# MSP432P401R.net
KiCad netlist of a schematic drawn in Altium Designer
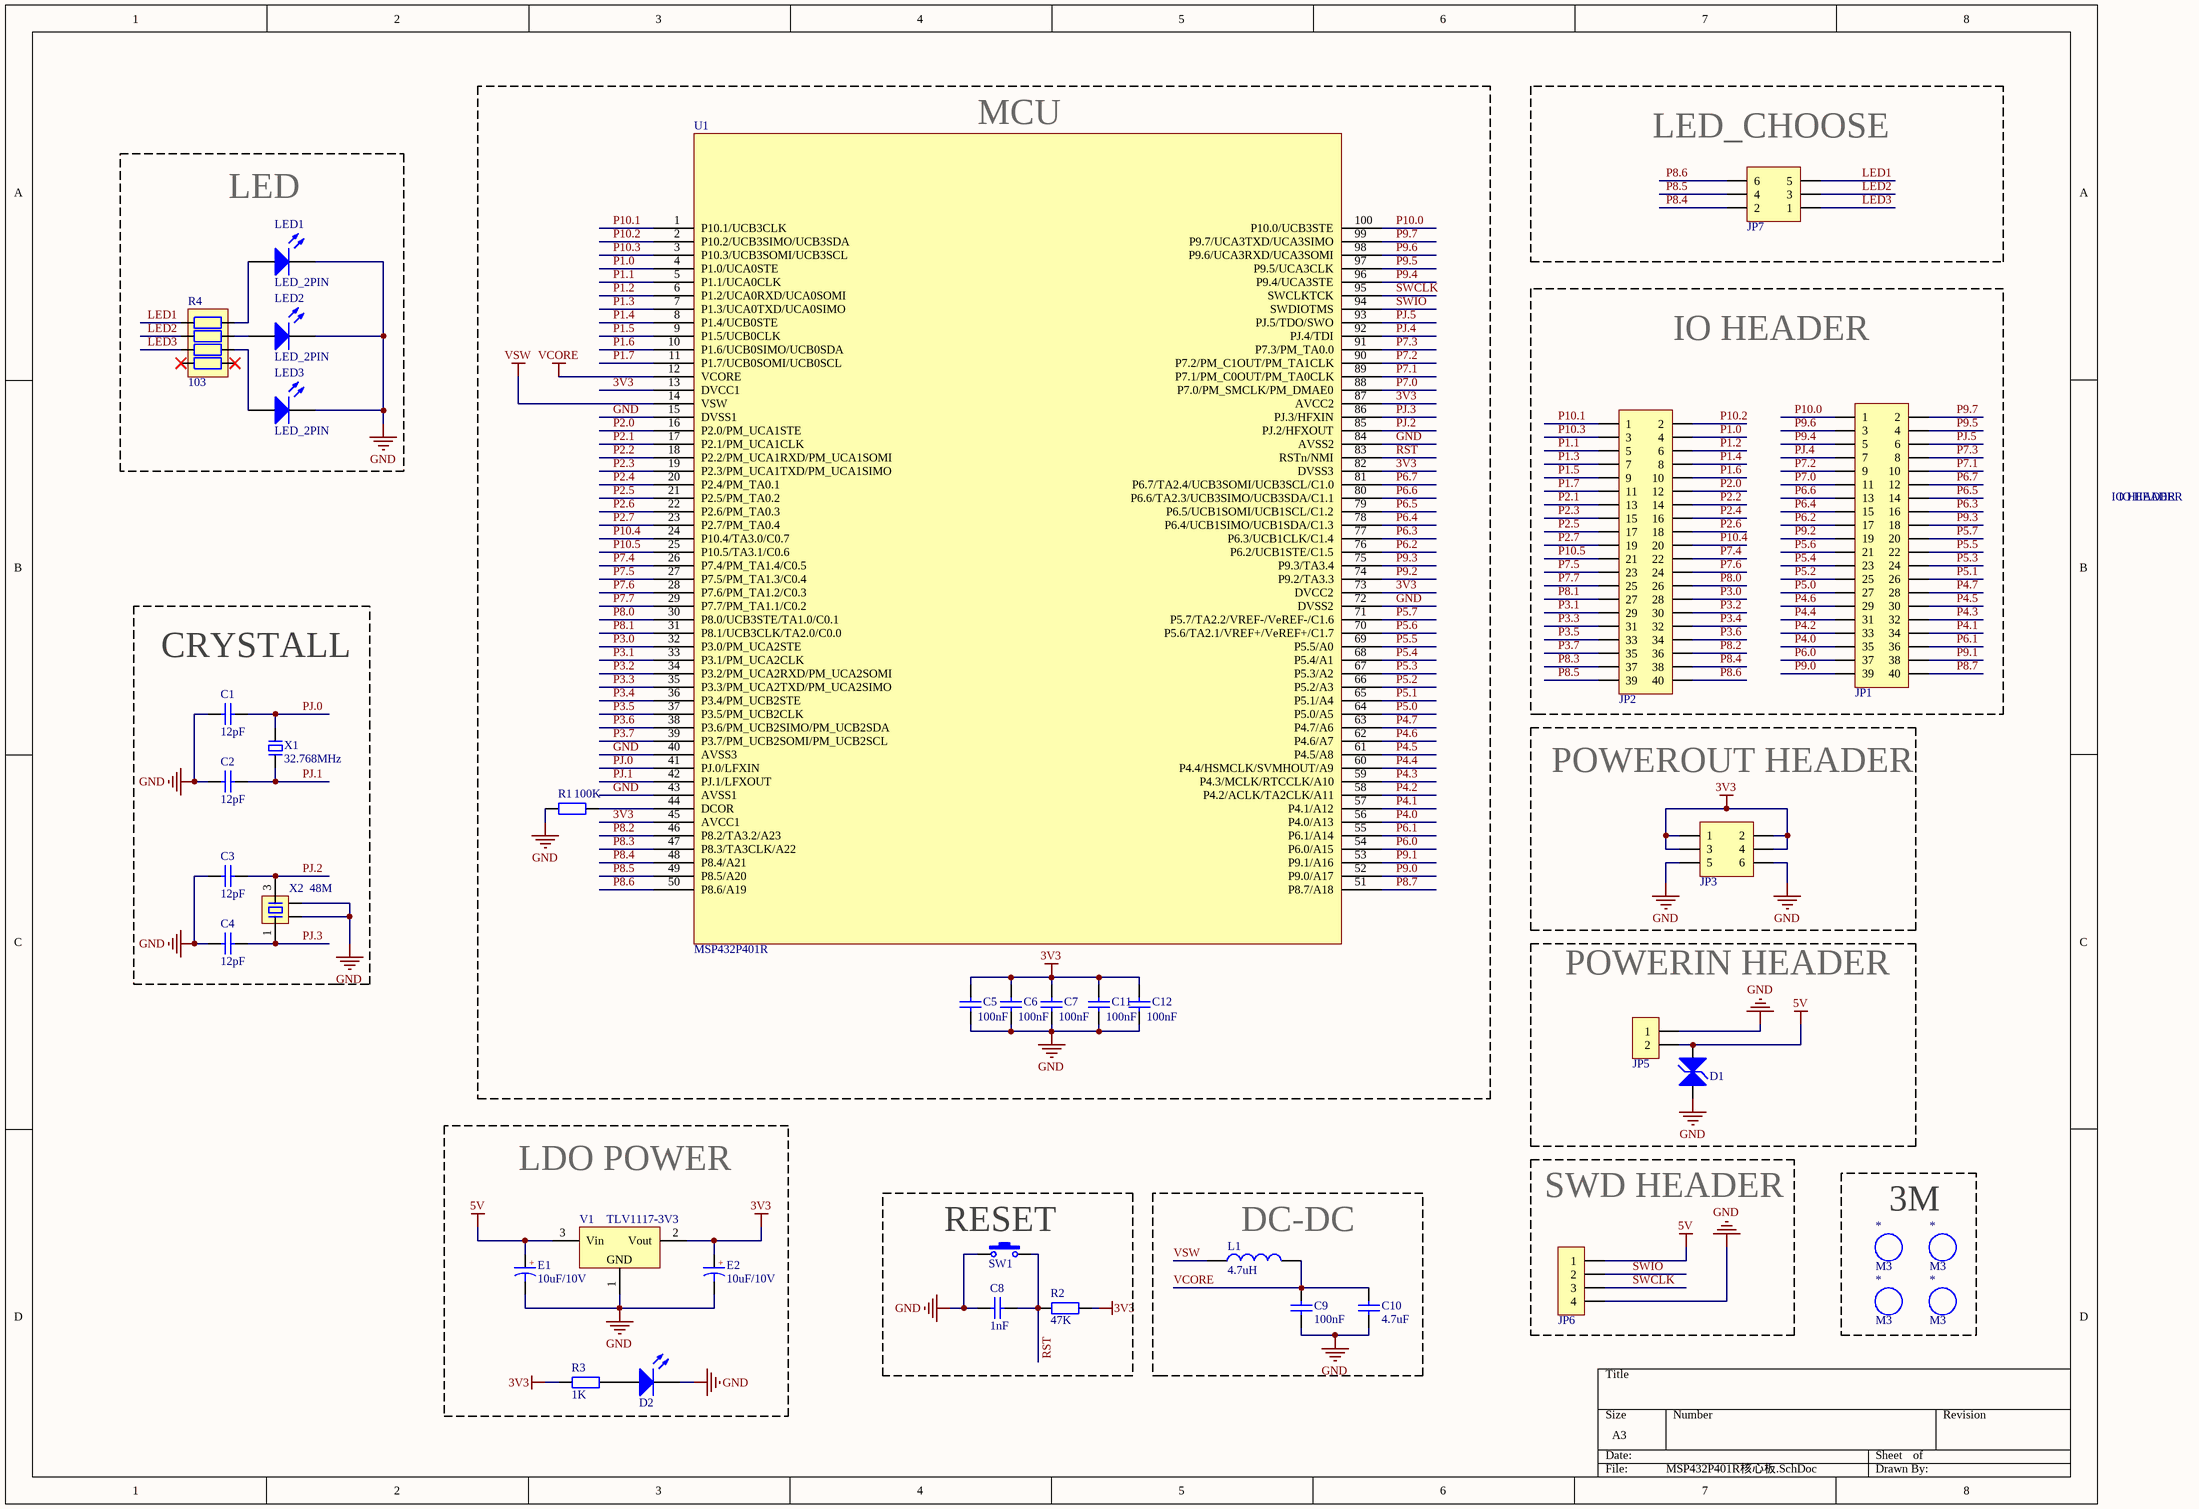
[diagram p0: MSP432P401R核心板.SchDoc]

(export (version "E")
  (design (tool "Eeschema 10.0.6"))
  (components
    (comp (ref "C1")
      (value "12pF")
      (footprint "C0603_L")
      (description "贴片电容")
      (libsource (lib "0.1 - 电阻-电容-电感") (part "C"))
    )
    (comp (ref "C2")
      (value "12pF")
      (footprint "C0603_L")
      (description "贴片电容")
      (libsource (lib "0.1 - 电阻-电容-电感") (part "C"))
    )
    (comp (ref "C3")
      (value "12pF")
      (footprint "C0603_L")
      (description "贴片电容")
      (libsource (lib "0.1 - 电阻-电容-电感") (part "C"))
    )
    (comp (ref "C4")
      (value "12pF")
      (footprint "C0603_L")
      (description "贴片电容")
      (libsource (lib "0.1 - 电阻-电容-电感") (part "C"))
    )
    (comp (ref "C5")
      (value "100nF")
      (footprint "C0603_L")
      (description "贴片电容")
      (libsource (lib "0.1 - 电阻-电容-电感") (part "C"))
    )
    (comp (ref "C6")
      (value "100nF")
      (footprint "C0603_L")
      (description "贴片电容")
      (libsource (lib "0.1 - 电阻-电容-电感") (part "C"))
    )
    (comp (ref "C7")
      (value "100nF")
      (footprint "C0603_L")
      (description "贴片电容")
      (libsource (lib "0.1 - 电阻-电容-电感") (part "C"))
    )
    (comp (ref "C8")
      (value "1nF")
      (footprint "C0603_L")
      (description "贴片电容")
      (libsource (lib "0.1 - 电阻-电容-电感") (part "C"))
    )
    (comp (ref "C9")
      (value "100nF")
      (footprint "C0603_L")
      (description "贴片电容")
      (libsource (lib "0.1 - 电阻-电容-电感") (part "C"))
    )
    (comp (ref "C10")
      (value "4.7uF")
      (footprint "C0603_L")
      (description "贴片电容")
      (libsource (lib "0.1 - 电阻-电容-电感") (part "C"))
    )
    (comp (ref "C11")
      (value "100nF")
      (footprint "C0603_L")
      (description "贴片电容")
      (libsource (lib "0.1 - 电阻-电容-电感") (part "C"))
    )
    (comp (ref "C12")
      (value "100nF")
      (footprint "C0603_L")
      (description "贴片电容")
      (libsource (lib "0.1 - 电阻-电容-电感") (part "C"))
    )
    (comp (ref "D1")
      (value "TVS")
      (footprint "SMA")
      (description "TVS保护")
      (libsource (lib "0.2 - 二极管-整流桥") (part "TVS"))
    )
    (comp (ref "D2")
      (value "LED")
      (footprint "LED0603_B")
      (description "发光二极管")
      (libsource (lib "0.3 - LED发光二极管") (part "LED"))
    )
    (comp (ref "E1")
      (value "10uF/10V")
      (footprint "CS 6*6 - B")
      (description "贴片固态电容")
      (libsource (lib "0.1 - 电阻-电容-电感") (part "CS_SMD"))
    )
    (comp (ref "E2")
      (value "10uF/10V")
      (footprint "CS 6*6 - B")
      (description "贴片固态电容")
      (libsource (lib "0.1 - 电阻-电容-电感") (part "CS_SMD"))
    )
    (comp (ref "JP1")
      (value "Header 2X11")
      (footprint "HDR2.54-LI-2x20P")
      (description "20*2P接插件")
      (libsource (lib "5.4 - 接插件-脚距2.54 (100mil) ") (part "Header 20X2"))
    )
    (comp (ref "JP2")
      (value "Header 2X11")
      (footprint "HDR2.54-LI-2x20P")
      (description "20*2P接插件")
      (libsource (lib "5.4 - 接插件-脚距2.54 (100mil) ") (part "Header 20X2"))
    )
    (comp (ref "JP3")
      (value "Header3X2")
      (footprint "HDR2.54-LI-2x3P")
      (description "3*2P接插件")
      (libsource (lib "") (part "Header 3X2_1"))
    )
    (comp (ref "JP5")
      (value "HDR-1X2")
      (footprint "PH2.0-WS-2P")
      (description "2P接插件")
      (libsource (lib "5.3 - 接插件-脚距2.0") (part "Header 2"))
    )
    (comp (ref "JP6")
      (value "HDR-1X4")
      (footprint "PH2.0-WS-4P")
      (description "4P接插件")
      (libsource (lib "5.3 - 接插件-脚距2.0") (part "Header 4"))
    )
    (comp (ref "JP7")
      (value "Header3X2")
      (footprint "HDR2.54-LI-2x3P")
      (description "3*2P接插件")
      (libsource (lib "5.4 - 接插件-脚距2.54 (100mil) ") (part "Header 3X2"))
    )
    (comp (ref "L1")
      (value "4.7uH")
      (footprint "L0603")
      (description "贴片小功率电感")
      (libsource (lib "0.1 - 电阻-电容-电感") (part "L"))
    )
    (comp (ref "LED1")
      (value "LED_2PIN")
      (footprint "LED0603_B")
      (description "2脚LED")
      (libsource (lib "0.3 - LED发光二极管") (part "LED_2PIN"))
    )
    (comp (ref "LED2")
      (value "LED_2PIN")
      (footprint "LED0603_G")
      (description "2脚LED")
      (libsource (lib "0.3 - LED发光二极管") (part "LED_2PIN"))
    )
    (comp (ref "LED3")
      (value "LED_2PIN")
      (footprint "LED0603_Y")
      (description "2脚LED")
      (libsource (lib "0.3 - LED发光二极管") (part "LED_2PIN"))
    )
    (comp (ref "R1")
      (value "100K")
      (footprint "R0603_L")
      (description "贴片电阻")
      (libsource (lib "0.1 - 电阻-电容-电感") (part "R"))
    )
    (comp (ref "R2")
      (value "47K")
      (footprint "R0603_L")
      (description "贴片电阻")
      (libsource (lib "0.1 - 电阻-电容-电感") (part "R"))
    )
    (comp (ref "R3")
      (value "1K")
      (footprint "R0603_L")
      (description "贴片电阻")
      (libsource (lib "0.1 - 电阻-电容-电感") (part "R"))
    )
    (comp (ref "R4")
      (value "103")
      (footprint "RCA-8P4R-0603")
      (description "贴片排阻")
      (libsource (lib "0.1 - 电阻-电容-电感") (part "R-8P4R"))
    )
    (comp (ref "SW1")
      (value "3x6x5")
      (footprint "SW SMD-3*6*2.5")
      (description "3x6轻触开关")
      (libsource (lib "0.7 - 常用按键-开关-蜂鸣器-电池") (part "TSW_2PIN"))
    )
    (comp (ref "U1")
      (value "MSP432P401R")
      (footprint "QFP100")
      (libsource (lib "3.7 - MSP430系列单片机") (part "MSP432P401R"))
    )
    (comp (ref "V1")
      (value "TLV1117-3V3")
      (footprint "SOT223_L")
      (description "三端稳压芯片")
      (libsource (lib "1.1 - 电源类芯片") (part "AMS1117"))
    )
    (comp (ref "X1")
      (value "32.768MHz")
      (footprint "OSC 3215-2P")
      (description "2脚无源脚晶振")
      (libsource (lib "0.5 - 保险丝-晶振-光耦") (part "XTAL-2P"))
    )
    (comp (ref "X2")
      (value "48M")
      (footprint "OSC 3225-4P")
      (description "4脚晶振")
      (libsource (lib "0.5 - 保险丝-晶振-光耦") (part "XTAL-4P"))
    )
  )
  (nets
    (net (code "1") (name "/LED1") (class "Default")
      (node (ref "JP7") (pin "5") (pinfunction "5_5") (pintype "passive"))
      (node (ref "R4") (pin "1") (pinfunction "1_1") (pintype "passive"))
    )
    (net (code "2") (name "/LED2") (class "Default")
      (node (ref "JP7") (pin "3") (pinfunction "3_3") (pintype "passive"))
      (node (ref "R4") (pin "2") (pinfunction "2_2") (pintype "passive"))
    )
    (net (code "3") (name "/LED3") (class "Default")
      (node (ref "JP7") (pin "1") (pinfunction "1_1") (pintype "passive"))
      (node (ref "R4") (pin "3") (pinfunction "3_3") (pintype "passive"))
    )
    (net (code "4") (name "/P1.0") (class "Default")
      (node (ref "JP2") (pin "4") (pinfunction "4_4") (pintype "passive"))
      (node (ref "U1") (pin "4") (pinfunction "P1.0/UCA0STE_4") (pintype "passive"))
    )
    (net (code "5") (name "/P1.1") (class "Default")
      (node (ref "JP2") (pin "5") (pinfunction "5_5") (pintype "passive"))
      (node (ref "U1") (pin "5") (pinfunction "P1.1/UCA0CLK_5") (pintype "passive"))
    )
    (net (code "6") (name "/P1.2") (class "Default")
      (node (ref "JP2") (pin "6") (pinfunction "6_6") (pintype "passive"))
      (node (ref "U1") (pin "6") (pinfunction "P1.2/UCA0RXD/UCA0SOMI_6") (pintype "passive"))
    )
    (net (code "7") (name "/P1.3") (class "Default")
      (node (ref "JP2") (pin "7") (pinfunction "7_7") (pintype "passive"))
      (node (ref "U1") (pin "7") (pinfunction "P1.3/UCA0TXD/UCA0SIMO_7") (pintype "passive"))
    )
    (net (code "8") (name "/P1.4") (class "Default")
      (node (ref "JP2") (pin "8") (pinfunction "8_8") (pintype "passive"))
      (node (ref "U1") (pin "8") (pinfunction "P1.4/UCB0STE_8") (pintype "passive"))
    )
    (net (code "9") (name "/P1.5") (class "Default")
      (node (ref "JP2") (pin "9") (pinfunction "9_9") (pintype "passive"))
      (node (ref "U1") (pin "9") (pinfunction "P1.5/UCB0CLK_9") (pintype "passive"))
    )
    (net (code "10") (name "/P1.6") (class "Default")
      (node (ref "JP2") (pin "10") (pinfunction "10_10") (pintype "passive"))
      (node (ref "U1") (pin "10") (pinfunction "P1.6/UCB0SIMO/UCB0SDA_10") (pintype "passive"))
    )
    (net (code "11") (name "/P1.7") (class "Default")
      (node (ref "JP2") (pin "11") (pinfunction "11_11") (pintype "passive"))
      (node (ref "U1") (pin "11") (pinfunction "P1.7/UCB0SOMI/UCB0SCL_11") (pintype "passive"))
    )
    (net (code "12") (name "/P2.0") (class "Default")
      (node (ref "JP2") (pin "12") (pinfunction "12_12") (pintype "passive"))
      (node (ref "U1") (pin "16") (pinfunction "P2.0/PM_UCA1STE_16") (pintype "passive"))
    )
    (net (code "13") (name "/P2.1") (class "Default")
      (node (ref "JP2") (pin "13") (pinfunction "13_13") (pintype "passive"))
      (node (ref "U1") (pin "17") (pinfunction "P2.1/PM_UCA1CLK_17") (pintype "passive"))
    )
    (net (code "14") (name "/P2.2") (class "Default")
      (node (ref "JP2") (pin "14") (pinfunction "14_14") (pintype "passive"))
      (node (ref "U1") (pin "18") (pinfunction "P2.2/PM_UCA1RXD/PM_UCA1SOMI_18") (pintype "passive"))
    )
    (net (code "15") (name "/P2.3") (class "Default")
      (node (ref "JP2") (pin "15") (pinfunction "15_15") (pintype "passive"))
      (node (ref "U1") (pin "19") (pinfunction "P2.3/PM_UCA1TXD/PM_UCA1SIMO_19") (pintype "passive"))
    )
    (net (code "16") (name "/P2.4") (class "Default")
      (node (ref "JP2") (pin "16") (pinfunction "16_16") (pintype "passive"))
      (node (ref "U1") (pin "20") (pinfunction "P2.4/PM_TA0.1_20") (pintype "passive"))
    )
    (net (code "17") (name "/P2.5") (class "Default")
      (node (ref "JP2") (pin "17") (pinfunction "17_17") (pintype "passive"))
      (node (ref "U1") (pin "21") (pinfunction "P2.5/PM_TA0.2_21") (pintype "passive"))
    )
    (net (code "18") (name "/P2.6") (class "Default")
      (node (ref "JP2") (pin "18") (pinfunction "18_18") (pintype "passive"))
      (node (ref "U1") (pin "22") (pinfunction "P2.6/PM_TA0.3_22") (pintype "passive"))
    )
    (net (code "19") (name "/P2.7") (class "Default")
      (node (ref "JP2") (pin "19") (pinfunction "19_19") (pintype "passive"))
      (node (ref "U1") (pin "23") (pinfunction "P2.7/PM_TA0.4_23") (pintype "passive"))
    )
    (net (code "20") (name "/P3.0") (class "Default")
      (node (ref "JP2") (pin "28") (pinfunction "28_28") (pintype "passive"))
      (node (ref "U1") (pin "32") (pinfunction "P3.0/PM_UCA2STE_32") (pintype "passive"))
    )
    (net (code "21") (name "/P3.1") (class "Default")
      (node (ref "JP2") (pin "29") (pinfunction "29_29") (pintype "passive"))
      (node (ref "U1") (pin "33") (pinfunction "P3.1/PM_UCA2CLK_33") (pintype "passive"))
    )
    (net (code "22") (name "/P3.2") (class "Default")
      (node (ref "JP2") (pin "30") (pinfunction "30_30") (pintype "passive"))
      (node (ref "U1") (pin "34") (pinfunction "P3.2/PM_UCA2RXD/PM_UCA2SOMI_34") (pintype "passive"))
    )
    (net (code "23") (name "/P3.3") (class "Default")
      (node (ref "JP2") (pin "31") (pinfunction "31_31") (pintype "passive"))
      (node (ref "U1") (pin "35") (pinfunction "P3.3/PM_UCA2TXD/PM_UCA2SIMO_35") (pintype "passive"))
    )
    (net (code "24") (name "/P3.4") (class "Default")
      (node (ref "JP2") (pin "32") (pinfunction "32_32") (pintype "passive"))
      (node (ref "U1") (pin "36") (pinfunction "P3.4/PM_UCB2STE_36") (pintype "passive"))
    )
    (net (code "25") (name "/P3.5") (class "Default")
      (node (ref "JP2") (pin "33") (pinfunction "33_33") (pintype "passive"))
      (node (ref "U1") (pin "37") (pinfunction "P3.5/PM_UCB2CLK_37") (pintype "passive"))
    )
    (net (code "26") (name "/P3.6") (class "Default")
      (node (ref "JP2") (pin "34") (pinfunction "34_34") (pintype "passive"))
      (node (ref "U1") (pin "38") (pinfunction "P3.6/PM_UCB2SIMO/PM_UCB2SDA_38") (pintype "passive"))
    )
    (net (code "27") (name "/P3.7") (class "Default")
      (node (ref "JP2") (pin "35") (pinfunction "35_35") (pintype "passive"))
      (node (ref "U1") (pin "39") (pinfunction "P3.7/PM_UCB2SOMI/PM_UCB2SCL_39") (pintype "passive"))
    )
    (net (code "28") (name "/P4.0") (class "Default")
      (node (ref "JP1") (pin "35") (pinfunction "35_35") (pintype "passive"))
      (node (ref "U1") (pin "56") (pinfunction "_P4.0/A13_56") (pintype "passive"))
    )
    (net (code "29") (name "/P4.1") (class "Default")
      (node (ref "JP1") (pin "34") (pinfunction "34_34") (pintype "passive"))
      (node (ref "U1") (pin "57") (pinfunction "P4.1/A12_57") (pintype "passive"))
    )
    (net (code "30") (name "/P4.2") (class "Default")
      (node (ref "JP1") (pin "33") (pinfunction "33_33") (pintype "passive"))
      (node (ref "U1") (pin "58") (pinfunction "_P4.2/ACLK/TA2CLK/A11_58") (pintype "passive"))
    )
    (net (code "31") (name "/P4.3") (class "Default")
      (node (ref "JP1") (pin "32") (pinfunction "32_32") (pintype "passive"))
      (node (ref "U1") (pin "59") (pinfunction "P4.3/MCLK/RTCCLK/A10_59") (pintype "passive"))
    )
    (net (code "32") (name "/P4.4") (class "Default")
      (node (ref "JP1") (pin "31") (pinfunction "31_31") (pintype "passive"))
      (node (ref "U1") (pin "60") (pinfunction "P4.4/HSMCLK/SVMHOUT/A9_60") (pintype "passive"))
    )
    (net (code "33") (name "/P4.5") (class "Default")
      (node (ref "JP1") (pin "30") (pinfunction "30_30") (pintype "passive"))
      (node (ref "U1") (pin "61") (pinfunction "P4.5/A8_61") (pintype "passive"))
    )
    (net (code "34") (name "/P4.6") (class "Default")
      (node (ref "JP1") (pin "29") (pinfunction "29_29") (pintype "passive"))
      (node (ref "U1") (pin "62") (pinfunction "P4.6/A7_62") (pintype "passive"))
    )
    (net (code "35") (name "/P4.7") (class "Default")
      (node (ref "JP1") (pin "28") (pinfunction "28_28") (pintype "passive"))
      (node (ref "U1") (pin "63") (pinfunction "P4.7/A6_63") (pintype "passive"))
    )
    (net (code "36") (name "/P5.0") (class "Default")
      (node (ref "JP1") (pin "27") (pinfunction "27_27") (pintype "passive"))
      (node (ref "U1") (pin "64") (pinfunction "P5.0/A5_64") (pintype "passive"))
    )
    (net (code "37") (name "/P5.1") (class "Default")
      (node (ref "JP1") (pin "26") (pinfunction "26_26") (pintype "passive"))
      (node (ref "U1") (pin "65") (pinfunction "P5.1/A4_65") (pintype "passive"))
    )
    (net (code "38") (name "/P5.2") (class "Default")
      (node (ref "JP1") (pin "25") (pinfunction "25_25") (pintype "passive"))
      (node (ref "U1") (pin "66") (pinfunction "P5.2/A3_66") (pintype "passive"))
    )
    (net (code "39") (name "/P5.3") (class "Default")
      (node (ref "JP1") (pin "24") (pinfunction "24_24") (pintype "passive"))
      (node (ref "U1") (pin "67") (pinfunction "P5.3/A2_67") (pintype "passive"))
    )
    (net (code "40") (name "/P5.4") (class "Default")
      (node (ref "JP1") (pin "23") (pinfunction "23_23") (pintype "passive"))
      (node (ref "U1") (pin "68") (pinfunction "P5.4/A1_68") (pintype "passive"))
    )
    (net (code "41") (name "/P5.5") (class "Default")
      (node (ref "JP1") (pin "22") (pinfunction "22_22") (pintype "passive"))
      (node (ref "U1") (pin "69") (pinfunction "P5.5/A0_69") (pintype "passive"))
    )
    (net (code "42") (name "/P5.6") (class "Default")
      (node (ref "JP1") (pin "21") (pinfunction "21_21") (pintype "passive"))
      (node (ref "U1") (pin "70") (pinfunction "_P5.6/TA2.1/VREF+/VeREF+/C1.7_70") (pintype "passive"))
    )
    (net (code "43") (name "/P5.7") (class "Default")
      (node (ref "JP1") (pin "20") (pinfunction "20_20") (pintype "passive"))
      (node (ref "U1") (pin "71") (pinfunction "P5.7/TA2.2/VREF-/VeREF-/C1.6_71") (pintype "passive"))
    )
    (net (code "44") (name "/P6.0") (class "Default")
      (node (ref "JP1") (pin "37") (pinfunction "37_37") (pintype "passive"))
      (node (ref "U1") (pin "54") (pinfunction "P6.0/A15_54") (pintype "passive"))
    )
    (net (code "45") (name "/P6.1") (class "Default")
      (node (ref "JP1") (pin "36") (pinfunction "36_36") (pintype "passive"))
      (node (ref "U1") (pin "55") (pinfunction "P6.1/A14_55") (pintype "passive"))
    )
    (net (code "46") (name "/P6.2") (class "Default")
      (node (ref "JP1") (pin "17") (pinfunction "17_17") (pintype "passive"))
      (node (ref "U1") (pin "76") (pinfunction "P6.2/UCB1STE/C1.5_76") (pintype "passive"))
    )
    (net (code "47") (name "/P6.3") (class "Default")
      (node (ref "JP1") (pin "16") (pinfunction "16_16") (pintype "passive"))
      (node (ref "U1") (pin "77") (pinfunction "P6.3/UCB1CLK/C1.4_77") (pintype "passive"))
    )
    (net (code "48") (name "/P6.4") (class "Default")
      (node (ref "JP1") (pin "15") (pinfunction "15_15") (pintype "passive"))
      (node (ref "U1") (pin "78") (pinfunction "P6.4/UCB1SIMO/UCB1SDA/C1.3_78") (pintype "passive"))
    )
    (net (code "49") (name "/P6.5") (class "Default")
      (node (ref "JP1") (pin "14") (pinfunction "14_14") (pintype "passive"))
      (node (ref "U1") (pin "79") (pinfunction "P6.5/UCB1SOMI/UCB1SCL/C1.2_79") (pintype "passive"))
    )
    (net (code "50") (name "/P6.6") (class "Default")
      (node (ref "JP1") (pin "13") (pinfunction "13_13") (pintype "passive"))
      (node (ref "U1") (pin "80") (pinfunction "P6.6/TA2.3/UCB3SIMO/UCB3SDA/C1.1_80") (pintype "passive"))
    )
    (net (code "51") (name "/P6.7") (class "Default")
      (node (ref "JP1") (pin "12") (pinfunction "12_12") (pintype "passive"))
      (node (ref "U1") (pin "81") (pinfunction "P6.7/TA2.4/UCB3SOMI/UCB3SCL/C1.0_81") (pintype "passive"))
    )
    (net (code "52") (name "/P7.0") (class "Default")
      (node (ref "JP1") (pin "11") (pinfunction "11_11") (pintype "passive"))
      (node (ref "U1") (pin "88") (pinfunction "P7.0/PM_SMCLK/PM_DMAE0_88") (pintype "passive"))
    )
    (net (code "53") (name "/P7.1") (class "Default")
      (node (ref "JP1") (pin "10") (pinfunction "10_10") (pintype "passive"))
      (node (ref "U1") (pin "89") (pinfunction "P7.1/PM_C0OUT/PM_TA0CLK_89") (pintype "passive"))
    )
    (net (code "54") (name "/P7.2") (class "Default")
      (node (ref "JP1") (pin "9") (pinfunction "9_9") (pintype "passive"))
      (node (ref "U1") (pin "90") (pinfunction "P7.2/PM_C1OUT/PM_TA1CLK_90") (pintype "passive"))
    )
    (net (code "55") (name "/P7.3") (class "Default")
      (node (ref "JP1") (pin "8") (pinfunction "8_8") (pintype "passive"))
      (node (ref "U1") (pin "91") (pinfunction "P7.3/PM_TA0.0_91") (pintype "passive"))
    )
    (net (code "56") (name "/P7.4") (class "Default")
      (node (ref "JP2") (pin "22") (pinfunction "22_22") (pintype "passive"))
      (node (ref "U1") (pin "26") (pinfunction "P7.4/PM_TA1.4/C0.5_26") (pintype "passive"))
    )
    (net (code "57") (name "/P7.5") (class "Default")
      (node (ref "JP2") (pin "23") (pinfunction "23_23") (pintype "passive"))
      (node (ref "U1") (pin "27") (pinfunction "P7.5/PM_TA1.3/C0.4_27") (pintype "passive"))
    )
    (net (code "58") (name "/P7.6") (class "Default")
      (node (ref "JP2") (pin "24") (pinfunction "24_24") (pintype "passive"))
      (node (ref "U1") (pin "28") (pinfunction "P7.6/PM_TA1.2/C0.3_28") (pintype "passive"))
    )
    (net (code "59") (name "/P7.7") (class "Default")
      (node (ref "JP2") (pin "25") (pinfunction "25_25") (pintype "passive"))
      (node (ref "U1") (pin "29") (pinfunction "P7.7/PM_TA1.1/C0.2_29") (pintype "passive"))
    )
    (net (code "60") (name "/P8.0") (class "Default")
      (node (ref "JP2") (pin "26") (pinfunction "26_26") (pintype "passive"))
      (node (ref "U1") (pin "30") (pinfunction "P8.0/UCB3STE/TA1.0/C0.1_30") (pintype "passive"))
    )
    (net (code "61") (name "/P8.1") (class "Default")
      (node (ref "JP2") (pin "27") (pinfunction "27_27") (pintype "passive"))
      (node (ref "U1") (pin "31") (pinfunction "P8.1/UCB3CLK/TA2.0/C0.0_31") (pintype "passive"))
    )
    (net (code "62") (name "/P8.2") (class "Default")
      (node (ref "JP2") (pin "36") (pinfunction "36_36") (pintype "passive"))
      (node (ref "U1") (pin "46") (pinfunction "P8.2/TA3.2/A23_46") (pintype "passive"))
    )
    (net (code "63") (name "/P8.3") (class "Default")
      (node (ref "JP2") (pin "37") (pinfunction "37_37") (pintype "passive"))
      (node (ref "U1") (pin "47") (pinfunction "P8.3/TA3CLK/A22_47") (pintype "passive"))
    )
    (net (code "64") (name "/P8.4") (class "Default")
      (node (ref "JP2") (pin "38") (pinfunction "38_38") (pintype "passive"))
      (node (ref "JP7") (pin "2") (pinfunction "2_2") (pintype "passive"))
      (node (ref "U1") (pin "48") (pinfunction "P8.4/A21_48") (pintype "passive"))
    )
    (net (code "65") (name "/P8.5") (class "Default")
      (node (ref "JP2") (pin "39") (pinfunction "39_39") (pintype "passive"))
      (node (ref "JP7") (pin "4") (pinfunction "4_4") (pintype "passive"))
      (node (ref "U1") (pin "49") (pinfunction "P8.5/A20_49") (pintype "passive"))
    )
    (net (code "66") (name "/P8.6") (class "Default")
      (node (ref "JP2") (pin "40") (pinfunction "40_40") (pintype "passive"))
      (node (ref "JP7") (pin "6") (pinfunction "6_6") (pintype "passive"))
      (node (ref "U1") (pin "50") (pinfunction "P8.6/A19_50") (pintype "passive"))
    )
    (net (code "67") (name "/P8.7") (class "Default")
      (node (ref "JP1") (pin "40") (pinfunction "40_40") (pintype "passive"))
      (node (ref "U1") (pin "51") (pinfunction "P8.7/A18_51") (pintype "passive"))
    )
    (net (code "68") (name "/P9.0") (class "Default")
      (node (ref "JP1") (pin "39") (pinfunction "39_39") (pintype "passive"))
      (node (ref "U1") (pin "52") (pinfunction "P9.0/A17_52") (pintype "passive"))
    )
    (net (code "69") (name "/P9.1") (class "Default")
      (node (ref "JP1") (pin "38") (pinfunction "38_38") (pintype "passive"))
      (node (ref "U1") (pin "53") (pinfunction "P9.1/A16_53") (pintype "passive"))
    )
    (net (code "70") (name "/P9.2") (class "Default")
      (node (ref "JP1") (pin "19") (pinfunction "19_19") (pintype "passive"))
      (node (ref "U1") (pin "74") (pinfunction "P9.2/TA3.3_74") (pintype "passive"))
    )
    (net (code "71") (name "/P9.3") (class "Default")
      (node (ref "JP1") (pin "18") (pinfunction "18_18") (pintype "passive"))
      (node (ref "U1") (pin "75") (pinfunction "P9.3/TA3.4_75") (pintype "passive"))
    )
    (net (code "72") (name "/P9.4") (class "Default")
      (node (ref "JP1") (pin "5") (pinfunction "5_5") (pintype "passive"))
      (node (ref "U1") (pin "96") (pinfunction "P9.4/UCA3STE_96") (pintype "passive"))
    )
    (net (code "73") (name "/P9.5") (class "Default")
      (node (ref "JP1") (pin "4") (pinfunction "4_4") (pintype "passive"))
      (node (ref "U1") (pin "97") (pinfunction "P9.5/UCA3CLK_97") (pintype "passive"))
    )
    (net (code "74") (name "/P9.6") (class "Default")
      (node (ref "JP1") (pin "3") (pinfunction "3_3") (pintype "passive"))
      (node (ref "U1") (pin "98") (pinfunction "P9.6/UCA3RXD/UCA3SOMI_98") (pintype "passive"))
    )
    (net (code "75") (name "/P9.7") (class "Default")
      (node (ref "JP1") (pin "2") (pinfunction "2_2") (pintype "passive"))
      (node (ref "U1") (pin "99") (pinfunction "P9.7/UCA3TXD/UCA3SIMO_99") (pintype "passive"))
    )
    (net (code "76") (name "/P10.0") (class "Default")
      (node (ref "JP1") (pin "1") (pinfunction "1_1") (pintype "passive"))
      (node (ref "U1") (pin "100") (pinfunction "P10.0/UCB3STE_100") (pintype "passive"))
    )
    (net (code "77") (name "/P10.1") (class "Default")
      (node (ref "JP2") (pin "1") (pinfunction "1_1") (pintype "passive"))
      (node (ref "U1") (pin "1") (pinfunction "P10.1/UCB3CLK_1") (pintype "passive"))
    )
    (net (code "78") (name "/P10.2") (class "Default")
      (node (ref "JP2") (pin "2") (pinfunction "2_2") (pintype "passive"))
      (node (ref "U1") (pin "2") (pinfunction "P10.2/UCB3SIMO/UCB3SDA_2") (pintype "passive"))
    )
    (net (code "79") (name "/P10.3") (class "Default")
      (node (ref "JP2") (pin "3") (pinfunction "3_3") (pintype "passive"))
      (node (ref "U1") (pin "3") (pinfunction "P10.3/UCB3SOMI/UCB3SCL_3") (pintype "passive"))
    )
    (net (code "80") (name "/P10.4") (class "Default")
      (node (ref "JP2") (pin "20") (pinfunction "20_20") (pintype "passive"))
      (node (ref "U1") (pin "24") (pinfunction "P10.4/TA3.0/C0.7_24") (pintype "passive"))
    )
    (net (code "81") (name "/P10.5") (class "Default")
      (node (ref "JP2") (pin "21") (pinfunction "21_21") (pintype "passive"))
      (node (ref "U1") (pin "25") (pinfunction "P10.5/TA3.1/C0.6_25") (pintype "passive"))
    )
    (net (code "82") (name "/PJ.0") (class "Default")
      (node (ref "C1") (pin "2") (pinfunction "2_2") (pintype "passive"))
      (node (ref "U1") (pin "41") (pinfunction "PJ.0/LFXIN_41") (pintype "passive"))
      (node (ref "X1") (pin "2") (pinfunction "2_2") (pintype "passive"))
    )
    (net (code "83") (name "/PJ.1") (class "Default")
      (node (ref "C2") (pin "2") (pinfunction "2_2") (pintype "passive"))
      (node (ref "U1") (pin "42") (pinfunction "PJ.1/LFXOUT_42") (pintype "passive"))
      (node (ref "X1") (pin "1") (pinfunction "1_1") (pintype "passive"))
    )
    (net (code "84") (name "/PJ.2") (class "Default")
      (node (ref "C3") (pin "2") (pinfunction "2_2") (pintype "passive"))
      (node (ref "U1") (pin "85") (pinfunction "PJ.2/HFXOUT_85") (pintype "passive"))
      (node (ref "X2") (pin "3") (pinfunction "3_3") (pintype "passive"))
    )
    (net (code "85") (name "/PJ.3") (class "Default")
      (node (ref "C4") (pin "2") (pinfunction "2_2") (pintype "passive"))
      (node (ref "U1") (pin "86") (pinfunction "PJ.3/HFXIN_86") (pintype "passive"))
      (node (ref "X2") (pin "1") (pinfunction "1_1") (pintype "passive"))
    )
    (net (code "86") (name "/PJ.4") (class "Default")
      (node (ref "JP1") (pin "7") (pinfunction "7_7") (pintype "passive"))
      (node (ref "U1") (pin "92") (pinfunction "PJ.4/TDI_92") (pintype "passive"))
    )
    (net (code "87") (name "/PJ.5") (class "Default")
      (node (ref "JP1") (pin "6") (pinfunction "6_6") (pintype "passive"))
      (node (ref "U1") (pin "93") (pinfunction "PJ.5/TDO/SWO_93") (pintype "passive"))
    )
    (net (code "88") (name "/RST") (class "Default")
      (node (ref "C8") (pin "2") (pinfunction "2_2") (pintype "passive"))
      (node (ref "R2") (pin "1") (pinfunction "1_1") (pintype "passive"))
      (node (ref "SW1") (pin "2") (pinfunction "2_2") (pintype "passive"))
      (node (ref "U1") (pin "83") (pinfunction "RSTn/NMI_83") (pintype "passive"))
    )
    (net (code "89") (name "/SWCLK") (class "Default")
      (node (ref "JP6") (pin "3") (pinfunction "3_3") (pintype "passive"))
      (node (ref "U1") (pin "95") (pinfunction "SWCLKTCK_95") (pintype "passive"))
    )
    (net (code "90") (name "/SWIO") (class "Default")
      (node (ref "JP6") (pin "2") (pinfunction "2_2") (pintype "passive"))
      (node (ref "U1") (pin "94") (pinfunction "SWDIOTMS_94") (pintype "passive"))
    )
    (net (code "91") (name "3V3") (class "Default")
      (node (ref "C11") (pin "2") (pinfunction "2_2") (pintype "passive"))
      (node (ref "C12") (pin "2") (pinfunction "2_2") (pintype "passive"))
      (node (ref "C5") (pin "2") (pinfunction "2_2") (pintype "passive"))
      (node (ref "C6") (pin "2") (pinfunction "2_2") (pintype "passive"))
      (node (ref "C7") (pin "2") (pinfunction "2_2") (pintype "passive"))
      (node (ref "E2") (pin "1") (pinfunction "1_1") (pintype "passive"))
      (node (ref "JP3") (pin "1") (pinfunction "1_1") (pintype "passive"))
      (node (ref "JP3") (pin "2") (pinfunction "2_2") (pintype "passive"))
      (node (ref "JP3") (pin "3") (pinfunction "3_3") (pintype "passive"))
      (node (ref "JP3") (pin "4") (pinfunction "4_4") (pintype "passive"))
      (node (ref "R2") (pin "2") (pinfunction "2_2") (pintype "passive"))
      (node (ref "R3") (pin "1") (pinfunction "1_1") (pintype "passive"))
      (node (ref "U1") (pin "13") (pinfunction "DVCC1_13") (pintype "passive"))
      (node (ref "U1") (pin "45") (pinfunction "AVCC1_45") (pintype "passive"))
      (node (ref "U1") (pin "73") (pinfunction "DVCC2_73") (pintype "passive"))
      (node (ref "U1") (pin "82") (pinfunction "DVSS3_82") (pintype "passive"))
      (node (ref "U1") (pin "87") (pinfunction "AVCC2_87") (pintype "passive"))
      (node (ref "V1") (pin "2") (pinfunction "Vout_2") (pintype "passive"))
    )
    (net (code "92") (name "5V") (class "Default")
      (node (ref "D1") (pin "2") (pinfunction "K_2") (pintype "passive"))
      (node (ref "E1") (pin "1") (pinfunction "1_1") (pintype "passive"))
      (node (ref "JP5") (pin "2") (pinfunction "2_2") (pintype "passive"))
      (node (ref "JP6") (pin "1") (pinfunction "1_1") (pintype "passive"))
      (node (ref "V1") (pin "3") (pinfunction "Vin_3") (pintype "passive"))
    )
    (net (code "93") (name "GND") (class "Default")
      (node (ref "C1") (pin "1") (pinfunction "1_1") (pintype "passive"))
      (node (ref "C10") (pin "1") (pinfunction "1_1") (pintype "passive"))
      (node (ref "C11") (pin "1") (pinfunction "1_1") (pintype "passive"))
      (node (ref "C12") (pin "1") (pinfunction "1_1") (pintype "passive"))
      (node (ref "C2") (pin "1") (pinfunction "1_1") (pintype "passive"))
      (node (ref "C3") (pin "1") (pinfunction "1_1") (pintype "passive"))
      (node (ref "C4") (pin "1") (pinfunction "1_1") (pintype "passive"))
      (node (ref "C5") (pin "1") (pinfunction "1_1") (pintype "passive"))
      (node (ref "C6") (pin "1") (pinfunction "1_1") (pintype "passive"))
      (node (ref "C7") (pin "1") (pinfunction "1_1") (pintype "passive"))
      (node (ref "C8") (pin "1") (pinfunction "1_1") (pintype "passive"))
      (node (ref "C9") (pin "1") (pinfunction "1_1") (pintype "passive"))
      (node (ref "D1") (pin "1") (pinfunction "A_1") (pintype "passive"))
      (node (ref "D2") (pin "2") (pinfunction "K_2") (pintype "passive"))
      (node (ref "E1") (pin "2") (pinfunction "2_2") (pintype "passive"))
      (node (ref "E2") (pin "2") (pinfunction "2_2") (pintype "passive"))
      (node (ref "JP3") (pin "5") (pinfunction "5_5") (pintype "passive"))
      (node (ref "JP3") (pin "6") (pinfunction "6_6") (pintype "passive"))
      (node (ref "JP5") (pin "1") (pinfunction "1_1") (pintype "passive"))
      (node (ref "JP6") (pin "4") (pinfunction "4_4") (pintype "passive"))
      (node (ref "LED1") (pin "2") (pinfunction "K_2") (pintype "passive"))
      (node (ref "LED2") (pin "2") (pinfunction "K_2") (pintype "passive"))
      (node (ref "LED3") (pin "2") (pinfunction "K_2") (pintype "passive"))
      (node (ref "R1") (pin "1") (pinfunction "1_1") (pintype "passive"))
      (node (ref "SW1") (pin "1") (pinfunction "1_1") (pintype "passive"))
      (node (ref "U1") (pin "15") (pinfunction "DVSS1_15") (pintype "passive"))
      (node (ref "U1") (pin "40") (pinfunction "AVSS3_40") (pintype "passive"))
      (node (ref "U1") (pin "43") (pinfunction "AVSS1_43") (pintype "passive"))
      (node (ref "U1") (pin "72") (pinfunction "DVSS2_72") (pintype "passive"))
      (node (ref "U1") (pin "84") (pinfunction "AVSS2_84") (pintype "passive"))
      (node (ref "V1") (pin "1") (pinfunction "GND_1") (pintype "passive"))
      (node (ref "X2") (pin "2") (pinfunction "2_2") (pintype "passive"))
      (node (ref "X2") (pin "4") (pinfunction "4_4") (pintype "passive"))
    )
    (net (code "94") (name "Net-(D2-A)") (class "Default")
      (node (ref "D2") (pin "1") (pinfunction "A_1") (pintype "passive"))
      (node (ref "R3") (pin "2") (pinfunction "2_2") (pintype "passive"))
    )
    (net (code "95") (name "Net-(LED1-A)") (class "Default")
      (node (ref "LED1") (pin "1") (pinfunction "A_1") (pintype "passive"))
      (node (ref "R4") (pin "8") (pinfunction "8_8") (pintype "passive"))
    )
    (net (code "96") (name "Net-(LED2-A)") (class "Default")
      (node (ref "LED2") (pin "1") (pinfunction "A_1") (pintype "passive"))
      (node (ref "R4") (pin "7") (pinfunction "7_7") (pintype "passive"))
    )
    (net (code "97") (name "Net-(LED3-A)") (class "Default")
      (node (ref "LED3") (pin "1") (pinfunction "A_1") (pintype "passive"))
      (node (ref "R4") (pin "6") (pinfunction "6_6") (pintype "passive"))
    )
    (net (code "98") (name "Net-(U1-DCOR)") (class "Default")
      (node (ref "R1") (pin "2") (pinfunction "2_2") (pintype "passive"))
      (node (ref "U1") (pin "44") (pinfunction "DCOR_44") (pintype "passive"))
    )
    (net (code "99") (name "VCORE") (class "Default")
      (node (ref "C10") (pin "2") (pinfunction "2_2") (pintype "passive"))
      (node (ref "C9") (pin "2") (pinfunction "2_2") (pintype "passive"))
      (node (ref "L1") (pin "2") (pinfunction "2_2") (pintype "passive"))
      (node (ref "U1") (pin "12") (pinfunction "VCORE_12") (pintype "passive"))
    )
    (net (code "100") (name "VSW") (class "Default")
      (node (ref "L1") (pin "1") (pinfunction "1_1") (pintype "passive"))
      (node (ref "U1") (pin "14") (pinfunction "VSW_14") (pintype "passive"))
    )
    (net (code "101") (name "unconnected-(R4-Pad4)") (class "Default")
      (node (ref "R4") (pin "4") (pinfunction "4_4") (pintype "passive+no_connect"))
    )
    (net (code "102") (name "unconnected-(R4-Pad5)") (class "Default")
      (node (ref "R4") (pin "5") (pinfunction "5_5") (pintype "passive+no_connect"))
    )
  )
)
